# DisplayModuleV1.net
KiCad netlist of a schematic drawn in EAGLE
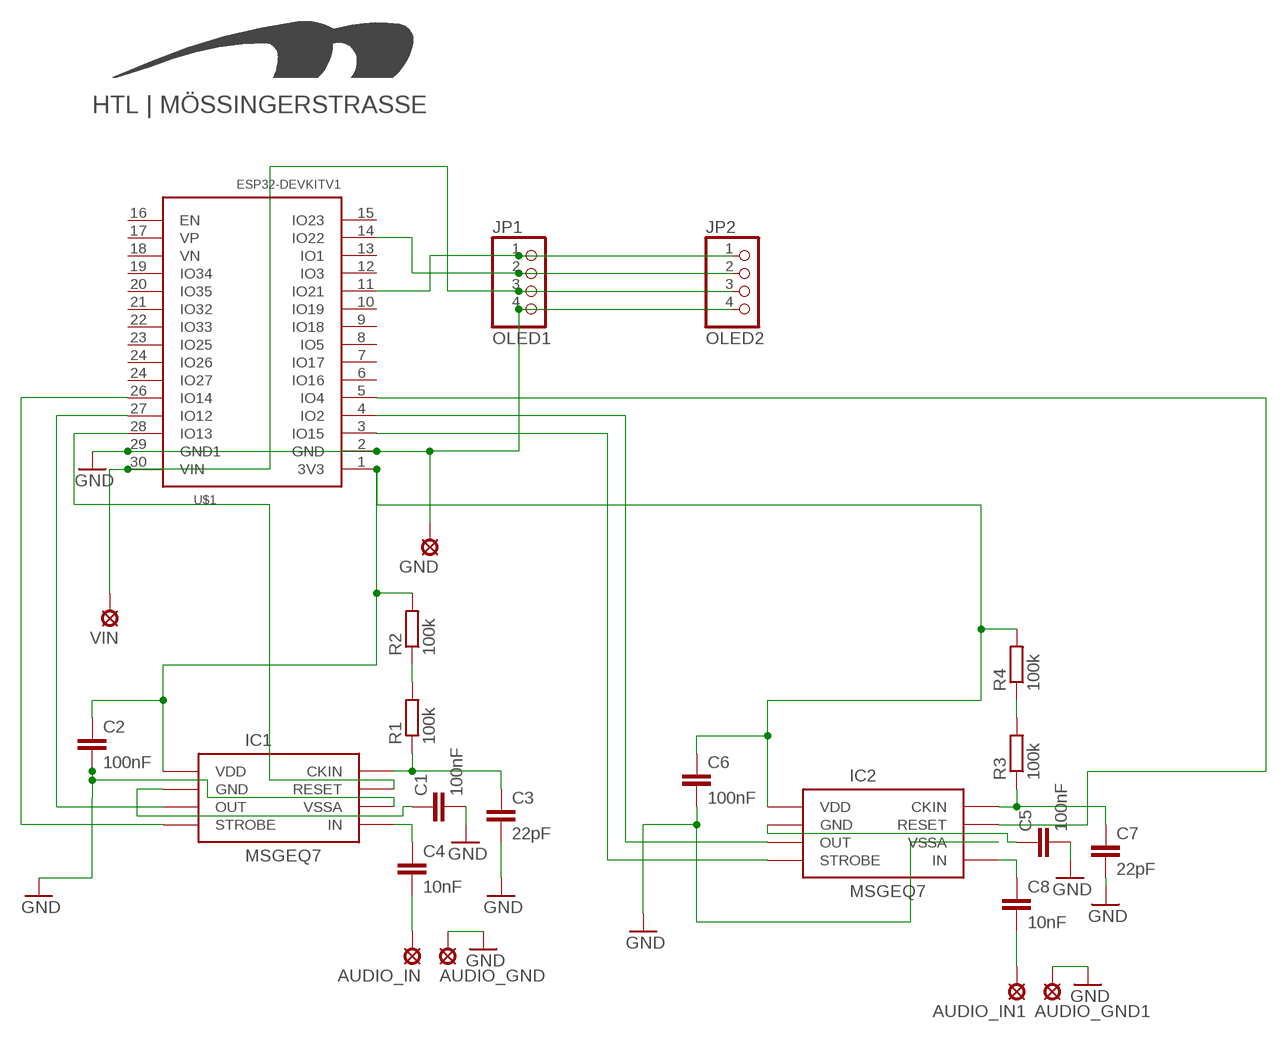
[diagram p0: schematic, sheet 1]

(export (version "E")
  (design (tool "Eeschema 10.0.6"))
  (components
    (comp (ref "AUDIO_GND")
      (value "LSP10")
      (footprint "eagle-import:LSP10")
      (libsource (lib "eagle-import") (part "LSP10"))
    )
    (comp (ref "AUDIO_GND1")
      (value "LSP10")
      (footprint "eagle-import:LSP10")
      (libsource (lib "eagle-import") (part "LSP10"))
    )
    (comp (ref "AUDIO_IN")
      (value "LSP10")
      (footprint "eagle-import:LSP10")
      (libsource (lib "eagle-import") (part "LSP10"))
    )
    (comp (ref "AUDIO_IN1")
      (value "LSP10")
      (footprint "eagle-import:LSP10")
      (libsource (lib "eagle-import") (part "LSP10"))
    )
    (comp (ref "C1")
      (value "100nF")
      (footprint "eagle-import:C050-030X075")
      (libsource (lib "eagle-import") (part "C-EU050-030X075"))
    )
    (comp (ref "C2")
      (value "100nF")
      (footprint "eagle-import:C050-030X075")
      (libsource (lib "eagle-import") (part "C-EU050-030X075"))
    )
    (comp (ref "C3")
      (value "22pF")
      (footprint "eagle-import:C050-030X075")
      (libsource (lib "eagle-import") (part "C-EU050-030X075"))
    )
    (comp (ref "C4")
      (value "10nF")
      (footprint "eagle-import:C050-030X075")
      (libsource (lib "eagle-import") (part "C-EU050-030X075"))
    )
    (comp (ref "C5")
      (value "100nF")
      (footprint "eagle-import:C050-030X075")
      (libsource (lib "eagle-import") (part "C-EU050-030X075"))
    )
    (comp (ref "C6")
      (value "100nF")
      (footprint "eagle-import:C050-030X075")
      (libsource (lib "eagle-import") (part "C-EU050-030X075"))
    )
    (comp (ref "C7")
      (value "22pF")
      (footprint "eagle-import:C050-030X075")
      (libsource (lib "eagle-import") (part "C-EU050-030X075"))
    )
    (comp (ref "C8")
      (value "10nF")
      (footprint "eagle-import:C050-030X075")
      (libsource (lib "eagle-import") (part "C-EU050-030X075"))
    )
    (comp (ref "GND")
      (value "LSP10")
      (footprint "eagle-import:LSP10")
      (libsource (lib "eagle-import") (part "LSP10"))
    )
    (comp (ref "IC1")
      (value "MSGEQ7DIP")
      (footprint "eagle-import:DIL08")
      (libsource (lib "eagle-import") (part "MSGEQ7DIP"))
    )
    (comp (ref "IC2")
      (value "MSGEQ7DIP")
      (footprint "eagle-import:DIL08")
      (libsource (lib "eagle-import") (part "MSGEQ7DIP"))
    )
    (comp (ref "JP1")
      (value "OLED1")
      (footprint "eagle-import:1X04")
      (libsource (lib "eagle-import") (part "PINHD-1X4"))
    )
    (comp (ref "JP2")
      (value "OLED2")
      (footprint "eagle-import:1X04")
      (libsource (lib "eagle-import") (part "PINHD-1X4"))
    )
    (comp (ref "R1")
      (value "100k")
      (footprint "eagle-import:0204_7")
      (libsource (lib "eagle-import") (part "R-EU_0204/7"))
    )
    (comp (ref "R2")
      (value "100k")
      (footprint "eagle-import:0204_7")
      (libsource (lib "eagle-import") (part "R-EU_0204/7"))
    )
    (comp (ref "R3")
      (value "100k")
      (footprint "eagle-import:0204_7")
      (libsource (lib "eagle-import") (part "R-EU_0204/7"))
    )
    (comp (ref "R4")
      (value "100k")
      (footprint "eagle-import:0204_7")
      (libsource (lib "eagle-import") (part "R-EU_0204/7"))
    )
    (comp (ref "U$1")
      (value "ESP32DEVKITV1")
      (footprint "eagle-import:ESP32-DEVKITV1")
      (libsource (lib "eagle-import") (part "ESP32DEVKITV1"))
    )
    (comp (ref "U$2")
      (value "HTL_LOGOBOTTOP_15MM")
      (footprint "eagle-import:LOGO_15")
      (libsource (lib "eagle-import") (part "HTL_LOGOBOTTOP_15MM"))
    )
    (comp (ref "VIN")
      (value "LSP10")
      (footprint "eagle-import:LSP10")
      (libsource (lib "eagle-import") (part "LSP10"))
    )
  )
  (nets
    (net (code "1") (name "GND") (class "Default")
      (node (ref "AUDIO_GND") (pin "MP") (pinfunction "MP_MP") (pintype "passive"))
      (node (ref "AUDIO_GND1") (pin "MP") (pinfunction "MP_MP") (pintype "passive"))
      (node (ref "C1") (pin "2") (pinfunction "2_2") (pintype "passive"))
      (node (ref "C2") (pin "2") (pinfunction "2_2") (pintype "passive"))
      (node (ref "C3") (pin "2") (pinfunction "2_2") (pintype "passive"))
      (node (ref "C5") (pin "2") (pinfunction "2_2") (pintype "passive"))
      (node (ref "C6") (pin "2") (pinfunction "2_2") (pintype "passive"))
      (node (ref "C7") (pin "2") (pinfunction "2_2") (pintype "passive"))
      (node (ref "GND") (pin "MP") (pinfunction "MP_MP") (pintype "passive"))
      (node (ref "IC1") (pin "2") (pinfunction "VSSA_2") (pintype "bidirectional"))
      (node (ref "IC2") (pin "2") (pinfunction "VSSA_2") (pintype "bidirectional"))
      (node (ref "JP1") (pin "4") (pinfunction "4_4") (pintype "passive"))
      (node (ref "JP2") (pin "4") (pinfunction "4_4") (pintype "passive"))
      (node (ref "U$1") (pin "2") (pinfunction "GND_2") (pintype "bidirectional"))
      (node (ref "U$1") (pin "29") (pinfunction "GND1_29") (pintype "bidirectional"))
    )
    (net (code "2") (name "Net-(AUDIO_IN-PadMP)") (class "Default")
      (node (ref "AUDIO_IN") (pin "MP") (pinfunction "MP_MP") (pintype "passive"))
      (node (ref "C4") (pin "2") (pinfunction "2_2") (pintype "passive"))
    )
    (net (code "3") (name "Net-(AUDIO_IN1-PadMP)") (class "Default")
      (node (ref "AUDIO_IN1") (pin "MP") (pinfunction "MP_MP") (pintype "passive"))
      (node (ref "C8") (pin "2") (pinfunction "2_2") (pintype "passive"))
    )
    (net (code "4") (name "Net-(IC1-CKIN)") (class "Default")
      (node (ref "C3") (pin "1") (pinfunction "1_1") (pintype "passive"))
      (node (ref "IC1") (pin "8") (pinfunction "CKIN_8") (pintype "bidirectional"))
      (node (ref "R1") (pin "1") (pinfunction "1_1") (pintype "passive"))
    )
    (net (code "5") (name "Net-(IC1-GND)") (class "Default")
      (node (ref "C1") (pin "1") (pinfunction "1_1") (pintype "passive"))
      (node (ref "IC1") (pin "6") (pinfunction "GND_6") (pintype "input"))
    )
    (net (code "6") (name "Net-(IC1-IN)") (class "Default")
      (node (ref "C4") (pin "1") (pinfunction "1_1") (pintype "passive"))
      (node (ref "IC1") (pin "5") (pinfunction "IN_5") (pintype "bidirectional"))
    )
    (net (code "7") (name "Net-(IC1-OUT)") (class "Default")
      (node (ref "IC1") (pin "3") (pinfunction "OUT_3") (pintype "input"))
      (node (ref "U$1") (pin "27") (pinfunction "IO12_27") (pintype "bidirectional"))
    )
    (net (code "8") (name "Net-(IC1-RESET)") (class "Default")
      (node (ref "IC1") (pin "7") (pinfunction "RESET_7") (pintype "bidirectional"))
      (node (ref "U$1") (pin "28") (pinfunction "IO13_28") (pintype "bidirectional"))
    )
    (net (code "9") (name "Net-(IC1-STROBE)") (class "Default")
      (node (ref "IC1") (pin "4") (pinfunction "STROBE_4") (pintype "input"))
      (node (ref "U$1") (pin "26") (pinfunction "IO14_26") (pintype "bidirectional"))
    )
    (net (code "10") (name "Net-(IC1-VDD)") (class "Default")
      (node (ref "C2") (pin "1") (pinfunction "1_1") (pintype "passive"))
      (node (ref "C6") (pin "1") (pinfunction "1_1") (pintype "passive"))
      (node (ref "IC1") (pin "1") (pinfunction "VDD_1") (pintype "input"))
      (node (ref "IC2") (pin "1") (pinfunction "VDD_1") (pintype "input"))
      (node (ref "R2") (pin "2") (pinfunction "2_2") (pintype "passive"))
      (node (ref "R4") (pin "2") (pinfunction "2_2") (pintype "passive"))
      (node (ref "U$1") (pin "1") (pinfunction "3V3_1") (pintype "bidirectional"))
    )
    (net (code "11") (name "Net-(IC2-CKIN)") (class "Default")
      (node (ref "C7") (pin "1") (pinfunction "1_1") (pintype "passive"))
      (node (ref "IC2") (pin "8") (pinfunction "CKIN_8") (pintype "bidirectional"))
      (node (ref "R3") (pin "1") (pinfunction "1_1") (pintype "passive"))
    )
    (net (code "12") (name "Net-(IC2-GND)") (class "Default")
      (node (ref "C5") (pin "1") (pinfunction "1_1") (pintype "passive"))
      (node (ref "IC2") (pin "6") (pinfunction "GND_6") (pintype "input"))
    )
    (net (code "13") (name "Net-(IC2-IN)") (class "Default")
      (node (ref "C8") (pin "1") (pinfunction "1_1") (pintype "passive"))
      (node (ref "IC2") (pin "5") (pinfunction "IN_5") (pintype "bidirectional"))
    )
    (net (code "14") (name "Net-(IC2-OUT)") (class "Default")
      (node (ref "IC2") (pin "3") (pinfunction "OUT_3") (pintype "input"))
      (node (ref "U$1") (pin "4") (pinfunction "IO2_4") (pintype "bidirectional"))
    )
    (net (code "15") (name "Net-(IC2-RESET)") (class "Default")
      (node (ref "IC2") (pin "7") (pinfunction "RESET_7") (pintype "bidirectional"))
      (node (ref "U$1") (pin "5") (pinfunction "IO4_5") (pintype "bidirectional"))
    )
    (net (code "16") (name "Net-(IC2-STROBE)") (class "Default")
      (node (ref "IC2") (pin "4") (pinfunction "STROBE_4") (pintype "input"))
      (node (ref "U$1") (pin "3") (pinfunction "IO15_3") (pintype "bidirectional"))
    )
    (net (code "17") (name "Net-(R1-Pad2)") (class "Default")
      (node (ref "R1") (pin "2") (pinfunction "2_2") (pintype "passive"))
      (node (ref "R2") (pin "1") (pinfunction "1_1") (pintype "passive"))
    )
    (net (code "18") (name "Net-(R3-Pad2)") (class "Default")
      (node (ref "R3") (pin "2") (pinfunction "2_2") (pintype "passive"))
      (node (ref "R4") (pin "1") (pinfunction "1_1") (pintype "passive"))
    )
    (net (code "19") (name "Net-(U$1-IO21)") (class "Default")
      (node (ref "JP1") (pin "1") (pinfunction "1_1") (pintype "passive"))
      (node (ref "JP2") (pin "1") (pinfunction "1_1") (pintype "passive"))
      (node (ref "U$1") (pin "11") (pinfunction "IO21_11") (pintype "bidirectional"))
    )
    (net (code "20") (name "Net-(U$1-IO22)") (class "Default")
      (node (ref "JP1") (pin "2") (pinfunction "2_2") (pintype "passive"))
      (node (ref "JP2") (pin "2") (pinfunction "2_2") (pintype "passive"))
      (node (ref "U$1") (pin "14") (pinfunction "IO22_14") (pintype "bidirectional"))
    )
    (net (code "21") (name "Net-(U$1-VIN)") (class "Default")
      (node (ref "JP1") (pin "3") (pinfunction "3_3") (pintype "passive"))
      (node (ref "JP2") (pin "3") (pinfunction "3_3") (pintype "passive"))
      (node (ref "U$1") (pin "30") (pinfunction "VIN_30") (pintype "bidirectional"))
      (node (ref "VIN") (pin "MP") (pinfunction "MP_MP") (pintype "passive"))
    )
    (net (code "22") (name "unconnected-(U$1-EN-Pad16)") (class "Default")
      (node (ref "U$1") (pin "16") (pinfunction "EN_16") (pintype "bidirectional"))
    )
    (net (code "23") (name "unconnected-(U$1-IO1-Pad13)") (class "Default")
      (node (ref "U$1") (pin "13") (pinfunction "IO1_13") (pintype "bidirectional"))
    )
    (net (code "24") (name "unconnected-(U$1-IO3-Pad12)") (class "Default")
      (node (ref "U$1") (pin "12") (pinfunction "IO3_12") (pintype "bidirectional"))
    )
    (net (code "25") (name "unconnected-(U$1-IO5-Pad8)") (class "Default")
      (node (ref "U$1") (pin "8") (pinfunction "IO5_8") (pintype "bidirectional"))
    )
    (net (code "26") (name "unconnected-(U$1-IO16-Pad6)") (class "Default")
      (node (ref "U$1") (pin "6") (pinfunction "IO16_6") (pintype "bidirectional"))
    )
    (net (code "27") (name "unconnected-(U$1-IO17-Pad7)") (class "Default")
      (node (ref "U$1") (pin "7") (pinfunction "IO17_7") (pintype "bidirectional"))
    )
    (net (code "28") (name "unconnected-(U$1-IO18-Pad9)") (class "Default")
      (node (ref "U$1") (pin "9") (pinfunction "IO18_9") (pintype "bidirectional"))
    )
    (net (code "29") (name "unconnected-(U$1-IO19-Pad10)") (class "Default")
      (node (ref "U$1") (pin "10") (pinfunction "IO19_10") (pintype "bidirectional"))
    )
    (net (code "30") (name "unconnected-(U$1-IO23-Pad15)") (class "Default")
      (node (ref "U$1") (pin "15") (pinfunction "IO23_15") (pintype "bidirectional"))
    )
    (net (code "31") (name "unconnected-(U$1-IO25-Pad23)") (class "Default")
      (node (ref "U$1") (pin "23") (pinfunction "IO25_23") (pintype "bidirectional"))
    )
    (net (code "32") (name "unconnected-(U$1-IO26-Pad24)") (class "Default")
      (node (ref "U$1") (pin "24") (pinfunction "IO26_24") (pintype "bidirectional"))
    )
    (net (code "33") (name "unconnected-(U$1-IO27-Pad24)") (class "Default")
      (node (ref "U$1") (pin "24") (pinfunction "IO27_24") (pintype "bidirectional"))
    )
    (net (code "34") (name "unconnected-(U$1-IO32-Pad21)") (class "Default")
      (node (ref "U$1") (pin "21") (pinfunction "IO32_21") (pintype "bidirectional"))
    )
    (net (code "35") (name "unconnected-(U$1-IO33-Pad22)") (class "Default")
      (node (ref "U$1") (pin "22") (pinfunction "IO33_22") (pintype "bidirectional"))
    )
    (net (code "36") (name "unconnected-(U$1-IO34-Pad19)") (class "Default")
      (node (ref "U$1") (pin "19") (pinfunction "IO34_19") (pintype "bidirectional"))
    )
    (net (code "37") (name "unconnected-(U$1-IO35-Pad20)") (class "Default")
      (node (ref "U$1") (pin "20") (pinfunction "IO35_20") (pintype "bidirectional"))
    )
    (net (code "38") (name "unconnected-(U$1-VN-Pad18)") (class "Default")
      (node (ref "U$1") (pin "18") (pinfunction "VN_18") (pintype "bidirectional"))
    )
    (net (code "39") (name "unconnected-(U$1-VP-Pad17)") (class "Default")
      (node (ref "U$1") (pin "17") (pinfunction "VP_17") (pintype "bidirectional"))
    )
  )
)
